# MCU.net
KiCad netlist of a schematic drawn in Altium Designer
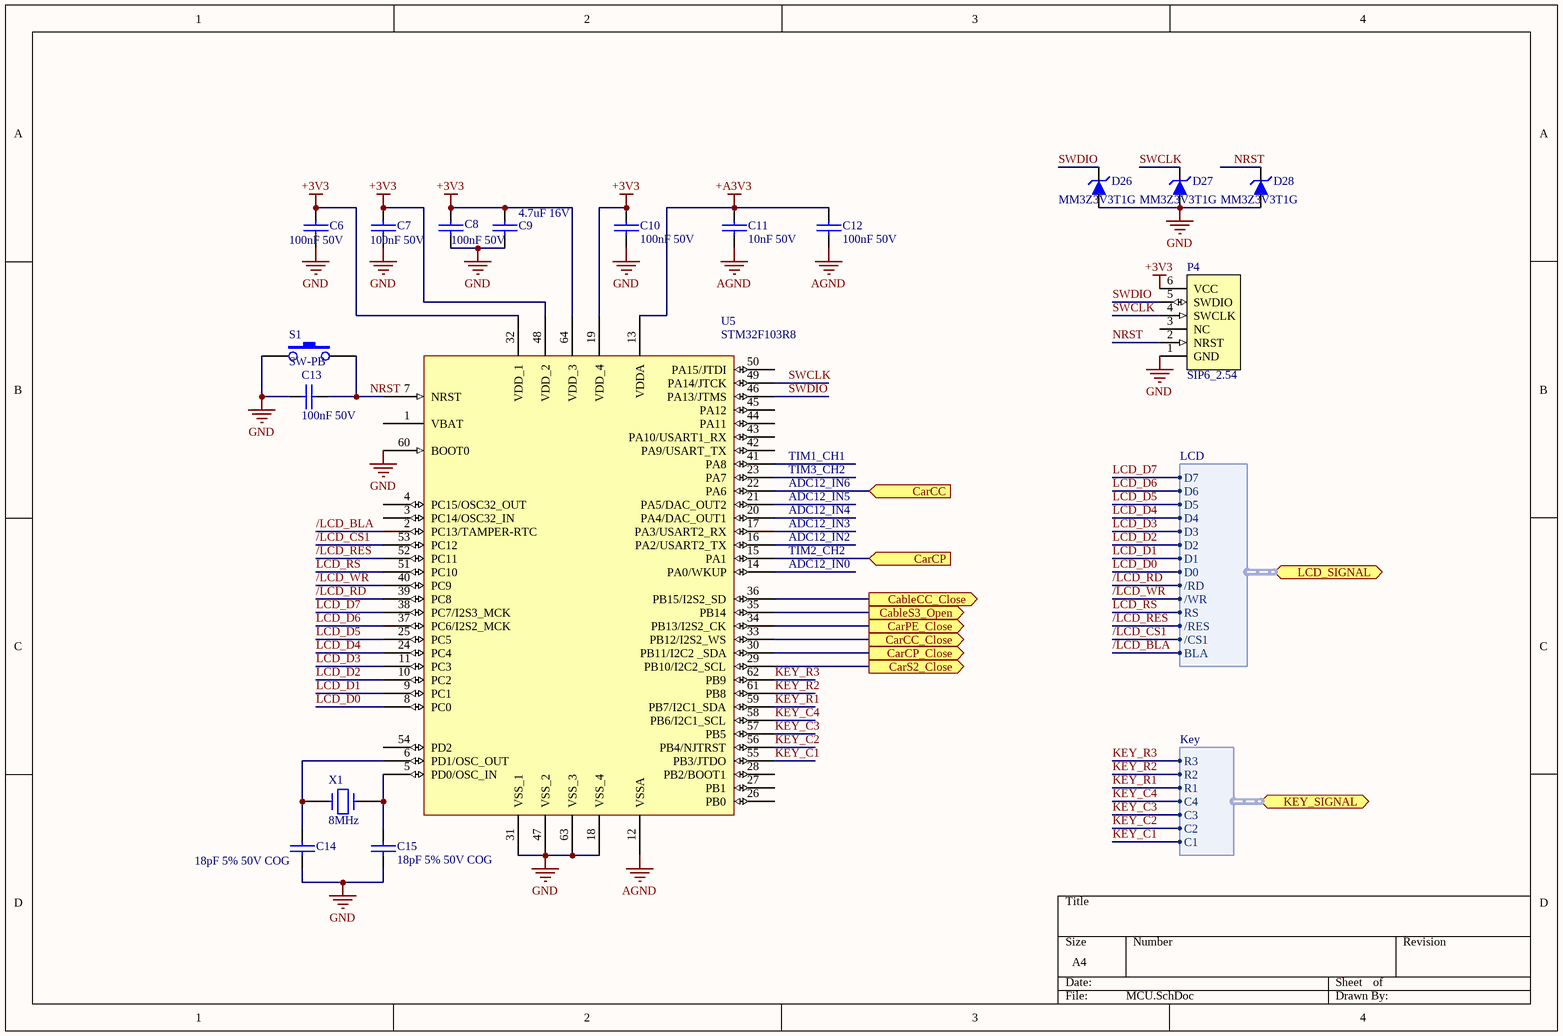
[diagram p0: MCU.SchDoc]

(export (version "E")
  (design (tool "Eeschema 10.0.6"))
  (components
    (comp (ref "C6")
      (value "100nF 50V")
      (footprint "Chip_Capacitor_N:CAPC2012N")
      (description "Capacitor")
      (libsource (lib "*") (part "CAP"))
    )
    (comp (ref "C7")
      (value "100nF 50V")
      (footprint "Chip_Capacitor_N:CAPC2012N")
      (description "Capacitor")
      (libsource (lib "*") (part "CAP"))
    )
    (comp (ref "C8")
      (value "100nF 50V")
      (footprint "Chip_Capacitor_N:CAPC2012N")
      (description "Capacitor")
      (libsource (lib "*") (part "CAP"))
    )
    (comp (ref "C9")
      (value "4.7uF 16V")
      (footprint "Chip_Capacitor_N:CAPC2012N")
      (description "Capacitor")
      (libsource (lib "*") (part "CAP"))
    )
    (comp (ref "C10")
      (value "100nF 50V")
      (footprint "Chip_Capacitor_N:CAPC2012N")
      (description "Capacitor")
      (libsource (lib "*") (part "CAP"))
    )
    (comp (ref "C11")
      (value "10nF 50V")
      (footprint "Chip_Capacitor_N:CAPC2012N")
      (description "Capacitor")
      (libsource (lib "*") (part "CAP"))
    )
    (comp (ref "C12")
      (value "100nF 50V")
      (footprint "Chip_Capacitor_N:CAPC2012N")
      (description "Capacitor")
      (libsource (lib "*") (part "CAP"))
    )
    (comp (ref "C13")
      (value "100nF 50V")
      (footprint "Chip_Capacitor_N:CAPC2012N")
      (description "Capacitor")
      (libsource (lib "*") (part "CAP"))
    )
    (comp (ref "C14")
      (value "18pF 5% 50V COG")
      (footprint "Chip_Capacitor_N:CAPC2012N")
      (description "Capacitor")
      (libsource (lib "*") (part "CAP"))
    )
    (comp (ref "C15")
      (value "18pF 5% 50V COG")
      (footprint "Chip_Capacitor_N:CAPC2012N")
      (description "Capacitor")
      (libsource (lib "*") (part "CAP"))
    )
    (comp (ref "D26")
      (value "MM3Z3V3T1G")
      (footprint "Small Outline Diode - 2 Gullwing Leads:SOD-323")
      (description "Zener diode")
      (fields (field (name "MANUFACTURER") "ON"))
      (libsource (lib "UserSchlib") (part "Zener Diode"))
    )
    (comp (ref "D27")
      (value "MM3Z3V3T1G")
      (footprint "Small Outline Diode - 2 Gullwing Leads:SOD-323")
      (description "Zener diode")
      (fields (field (name "MANUFACTURER") "ON"))
      (libsource (lib "UserSchlib") (part "Zener Diode"))
    )
    (comp (ref "D28")
      (value "MM3Z3V3T1G")
      (footprint "Small Outline Diode - 2 Gullwing Leads:SOD-323")
      (description "Zener diode")
      (fields (field (name "MANUFACTURER") "ON"))
      (libsource (lib "UserSchlib") (part "Zener Diode"))
    )
    (comp (ref "P4")
      (value "SIP6_2.54")
      (footprint "UserPcbLib:REAL_SIP6_2.54")
      (description "SW debug connector")
      (libsource (lib "UserSchlib") (part "SWD-Connector"))
    )
    (comp (ref "S1") (value "SW-PB") (footprint "UserPcbLib:SW5X7") (libsource (lib "*") (part "SW-PB")))
    (comp (ref "U5")
      (value "STM32F103R8")
      (footprint "ST-Microelectronics Footprints:TQFP64_M")
      (libsource (lib "Peter") (part "STM32F105RX"))
    )
    (comp (ref "X1")
      (value "8MHz")
      (footprint "ATSM-49")
      (description "晶振")
      (libsource (lib "*") (part "CRYSTAL"))
    )
  )
  (nets
    (net (code "3") (name "+3V3") (class "Default")
      (node (ref "C10") (pin "1") (pinfunction "1_1") (pintype "passive"))
      (node (ref "C6") (pin "2") (pinfunction "2_2") (pintype "passive"))
      (node (ref "C7") (pin "1") (pinfunction "1_1") (pintype "passive"))
      (node (ref "C8") (pin "1") (pinfunction "1_1") (pintype "passive"))
      (node (ref "C9") (pin "1") (pinfunction "1_1") (pintype "passive"))
      (node (ref "P4") (pin "6") (pinfunction "VCC_6") (pintype "power_in"))
      (node (ref "U5") (pin "19") (pinfunction "VDD_4_19") (pintype "power_in"))
      (node (ref "U5") (pin "32") (pinfunction "VDD_1_32") (pintype "power_in"))
      (node (ref "U5") (pin "48") (pinfunction "VDD_2_48") (pintype "power_in"))
      (node (ref "U5") (pin "64") (pinfunction "VDD_3_64") (pintype "power_in"))
    )
    (net (code "4") (name "+A3V3") (class "Default")
      (node (ref "C11") (pin "1") (pinfunction "1_1") (pintype "passive"))
      (node (ref "C12") (pin "1") (pinfunction "1_1") (pintype "passive"))
      (node (ref "U5") (pin "13") (pinfunction "VDDA_13") (pintype "power_in"))
    )
    (net (code "5") (name "/CableCC_Close") (class "Default")
      (node (ref "U5") (pin "36") (pinfunction "PB15/I2S2_SD_36") (pintype "bidirectional"))
    )
    (net (code "6") (name "/CableS3_Open") (class "Default")
      (node (ref "U5") (pin "35") (pinfunction "PB14_35") (pintype "bidirectional"))
    )
    (net (code "7") (name "/CarCC") (class "Default")
      (node (ref "U5") (pin "22") (pinfunction "PA6_22") (pintype "bidirectional"))
    )
    (net (code "8") (name "/CarCC_Close") (class "Default")
      (node (ref "U5") (pin "33") (pinfunction "PB12/I2S2_WS_33") (pintype "bidirectional"))
    )
    (net (code "9") (name "/CarCP") (class "Default")
      (node (ref "U5") (pin "15") (pinfunction "PA1_15") (pintype "bidirectional"))
    )
    (net (code "10") (name "/CarCP_Close") (class "Default")
      (node (ref "U5") (pin "30") (pinfunction "PB11/I2C2__SDA_30") (pintype "bidirectional"))
    )
    (net (code "11") (name "/CarPE_Close") (class "Default")
      (node (ref "U5") (pin "34") (pinfunction "PB13/I2S2_CK_34") (pintype "bidirectional"))
    )
    (net (code "12") (name "/CarS2_Close") (class "Default")
      (node (ref "U5") (pin "29") (pinfunction "PB10/I2C2_SCL_29") (pintype "bidirectional"))
    )
    (net (code "13") (name "/KEY_C1") (class "Default")
      (node (ref "U5") (pin "55") (pinfunction "PB3/JTDO_55") (pintype "bidirectional"))
    )
    (net (code "14") (name "/KEY_C2") (class "Default")
      (node (ref "U5") (pin "56") (pinfunction "PB4/NJTRST_56") (pintype "bidirectional"))
    )
    (net (code "15") (name "/KEY_C3") (class "Default")
      (node (ref "U5") (pin "57") (pinfunction "PB5_57") (pintype "bidirectional"))
    )
    (net (code "16") (name "/KEY_C4") (class "Default")
      (node (ref "U5") (pin "58") (pinfunction "PB6/I2C1_SCL_58") (pintype "bidirectional"))
    )
    (net (code "17") (name "/KEY_R1") (class "Default")
      (node (ref "U5") (pin "59") (pinfunction "PB7/I2C1_SDA_59") (pintype "bidirectional"))
    )
    (net (code "18") (name "/KEY_R2") (class "Default")
      (node (ref "U5") (pin "61") (pinfunction "PB8_61") (pintype "bidirectional"))
    )
    (net (code "19") (name "/KEY_R3") (class "Default")
      (node (ref "U5") (pin "62") (pinfunction "PB9_62") (pintype "bidirectional"))
    )
    (net (code "20") (name "/LCD_D0") (class "Default")
      (node (ref "U5") (pin "8") (pinfunction "PC0_8") (pintype "bidirectional"))
    )
    (net (code "21") (name "/LCD_D1") (class "Default")
      (node (ref "U5") (pin "9") (pinfunction "PC1_9") (pintype "bidirectional"))
    )
    (net (code "22") (name "/LCD_D2") (class "Default")
      (node (ref "U5") (pin "10") (pinfunction "PC2_10") (pintype "bidirectional"))
    )
    (net (code "23") (name "/LCD_D3") (class "Default")
      (node (ref "U5") (pin "11") (pinfunction "PC3_11") (pintype "bidirectional"))
    )
    (net (code "24") (name "/LCD_D4") (class "Default")
      (node (ref "U5") (pin "24") (pinfunction "PC4_24") (pintype "bidirectional"))
    )
    (net (code "25") (name "/LCD_D5") (class "Default")
      (node (ref "U5") (pin "25") (pinfunction "PC5_25") (pintype "bidirectional"))
    )
    (net (code "26") (name "/LCD_D6") (class "Default")
      (node (ref "U5") (pin "37") (pinfunction "PC6/I2S2_MCK_37") (pintype "bidirectional"))
    )
    (net (code "27") (name "/LCD_D7") (class "Default")
      (node (ref "U5") (pin "38") (pinfunction "PC7/I2S3_MCK_38") (pintype "bidirectional"))
    )
    (net (code "28") (name "/LCD_RS") (class "Default")
      (node (ref "U5") (pin "51") (pinfunction "PC10_51") (pintype "bidirectional"))
    )
    (net (code "29") (name "/NRST") (class "Default")
      (node (ref "C13") (pin "1") (pinfunction "1_1") (pintype "passive"))
      (node (ref "D28") (pin "1") (pinfunction "K_1") (pintype "passive"))
      (node (ref "P4") (pin "2") (pinfunction "NRST_2") (pintype "input"))
      (node (ref "S1") (pin "2") (pinfunction "2_2") (pintype "passive"))
      (node (ref "U5") (pin "7") (pinfunction "NRST_7") (pintype "input"))
    )
    (net (code "30") (name "/SWCLK") (class "Default")
      (node (ref "D27") (pin "1") (pinfunction "K_1") (pintype "passive"))
      (node (ref "P4") (pin "4") (pinfunction "SWCLK_4") (pintype "input"))
      (node (ref "U5") (pin "49") (pinfunction "PA14/JTCK_49") (pintype "bidirectional"))
    )
    (net (code "31") (name "/SWDIO") (class "Default")
      (node (ref "D26") (pin "1") (pinfunction "K_1") (pintype "passive"))
      (node (ref "P4") (pin "5") (pinfunction "SWDIO_5") (pintype "bidirectional"))
      (node (ref "U5") (pin "46") (pinfunction "PA13/JTMS_46") (pintype "bidirectional"))
    )
    (net (code "34") (name "/{slash}LCD_BLA") (class "Default")
      (node (ref "U5") (pin "2") (pinfunction "PC13/TAMPER-RTC_2") (pintype "bidirectional"))
    )
    (net (code "35") (name "/{slash}LCD_CS1") (class "Default")
      (node (ref "U5") (pin "53") (pinfunction "PC12_53") (pintype "bidirectional"))
    )
    (net (code "36") (name "/{slash}LCD_RD") (class "Default")
      (node (ref "U5") (pin "39") (pinfunction "PC8_39") (pintype "bidirectional"))
    )
    (net (code "37") (name "/{slash}LCD_RES") (class "Default")
      (node (ref "U5") (pin "52") (pinfunction "PC11_52") (pintype "bidirectional"))
    )
    (net (code "38") (name "/{slash}LCD_WR") (class "Default")
      (node (ref "U5") (pin "40") (pinfunction "PC9_40") (pintype "bidirectional"))
    )
    (net (code "39") (name "AGND") (class "Default")
      (node (ref "C11") (pin "2") (pinfunction "2_2") (pintype "passive"))
      (node (ref "C12") (pin "2") (pinfunction "2_2") (pintype "passive"))
      (node (ref "U5") (pin "12") (pinfunction "VSSA_12") (pintype "power_in"))
    )
    (net (code "40") (name "GND") (class "Default")
      (node (ref "C10") (pin "2") (pinfunction "2_2") (pintype "passive"))
      (node (ref "C13") (pin "2") (pinfunction "2_2") (pintype "passive"))
      (node (ref "C14") (pin "2") (pinfunction "2_2") (pintype "passive"))
      (node (ref "C15") (pin "1") (pinfunction "1_1") (pintype "passive"))
      (node (ref "C6") (pin "1") (pinfunction "1_1") (pintype "passive"))
      (node (ref "C7") (pin "2") (pinfunction "2_2") (pintype "passive"))
      (node (ref "C8") (pin "2") (pinfunction "2_2") (pintype "passive"))
      (node (ref "C9") (pin "2") (pinfunction "2_2") (pintype "passive"))
      (node (ref "D26") (pin "2") (pinfunction "A_2") (pintype "passive"))
      (node (ref "D27") (pin "2") (pinfunction "A_2") (pintype "passive"))
      (node (ref "D28") (pin "2") (pinfunction "A_2") (pintype "passive"))
      (node (ref "P4") (pin "1") (pinfunction "GND_1") (pintype "power_in"))
      (node (ref "S1") (pin "1") (pinfunction "1_1") (pintype "passive"))
      (node (ref "U5") (pin "18") (pinfunction "VSS_4_18") (pintype "power_in"))
      (node (ref "U5") (pin "31") (pinfunction "VSS_1_31") (pintype "power_in"))
      (node (ref "U5") (pin "47") (pinfunction "VSS_2_47") (pintype "power_in"))
      (node (ref "U5") (pin "60") (pinfunction "BOOT0_60") (pintype "input"))
      (node (ref "U5") (pin "63") (pinfunction "VSS_3_63") (pintype "power_in"))
    )
    (net (code "41") (name "Net-(U5-PD0{slash}OSC_IN)") (class "Default")
      (node (ref "C15") (pin "2") (pinfunction "2_2") (pintype "passive"))
      (node (ref "U5") (pin "5") (pinfunction "PD0/OSC_IN_5") (pintype "bidirectional"))
      (node (ref "X1") (pin "2") (pinfunction "2_2") (pintype "passive"))
    )
    (net (code "42") (name "Net-(U5-PD1{slash}OSC_OUT)") (class "Default")
      (node (ref "C14") (pin "1") (pinfunction "1_1") (pintype "passive"))
      (node (ref "U5") (pin "6") (pinfunction "PD1/OSC_OUT_6") (pintype "bidirectional"))
      (node (ref "X1") (pin "1") (pinfunction "1_1") (pintype "passive"))
    )
    (net (code "43") (name "unconnected-(P4-NC-Pad3)") (class "Default")
      (node (ref "P4") (pin "3") (pinfunction "NC_3") (pintype "power_in"))
    )
    (net (code "44") (name "unconnected-(U5-PA0{slash}WKUP-Pad14)") (class "Default")
      (node (ref "U5") (pin "14") (pinfunction "PA0/WKUP_14") (pintype "bidirectional"))
    )
    (net (code "45") (name "unconnected-(U5-PA2{slash}USART2_TX-Pad16)") (class "Default")
      (node (ref "U5") (pin "16") (pinfunction "PA2/USART2_TX_16") (pintype "bidirectional"))
    )
    (net (code "46") (name "unconnected-(U5-PA3{slash}USART2_RX-Pad17)") (class "Default")
      (node (ref "U5") (pin "17") (pinfunction "PA3/USART2_RX_17") (pintype "bidirectional"))
    )
    (net (code "47") (name "unconnected-(U5-PA4{slash}DAC_OUT1-Pad20)") (class "Default")
      (node (ref "U5") (pin "20") (pinfunction "PA4/DAC_OUT1_20") (pintype "bidirectional"))
    )
    (net (code "48") (name "unconnected-(U5-PA5{slash}DAC_OUT2-Pad21)") (class "Default")
      (node (ref "U5") (pin "21") (pinfunction "PA5/DAC_OUT2_21") (pintype "bidirectional"))
    )
    (net (code "49") (name "unconnected-(U5-PA7-Pad23)") (class "Default")
      (node (ref "U5") (pin "23") (pinfunction "PA7_23") (pintype "bidirectional"))
    )
    (net (code "50") (name "unconnected-(U5-PA8-Pad41)") (class "Default")
      (node (ref "U5") (pin "41") (pinfunction "PA8_41") (pintype "bidirectional"))
    )
    (net (code "51") (name "unconnected-(U5-PA9{slash}USART_TX-Pad42)") (class "Default")
      (node (ref "U5") (pin "42") (pinfunction "PA9/USART_TX_42") (pintype "bidirectional"))
    )
    (net (code "52") (name "unconnected-(U5-PA10{slash}USART1_RX-Pad43)") (class "Default")
      (node (ref "U5") (pin "43") (pinfunction "PA10/USART1_RX_43") (pintype "bidirectional"))
    )
    (net (code "53") (name "unconnected-(U5-PA11-Pad44)") (class "Default")
      (node (ref "U5") (pin "44") (pinfunction "PA11_44") (pintype "bidirectional"))
    )
    (net (code "54") (name "unconnected-(U5-PA12-Pad45)") (class "Default")
      (node (ref "U5") (pin "45") (pinfunction "PA12_45") (pintype "bidirectional"))
    )
    (net (code "55") (name "unconnected-(U5-PA15{slash}JTDI-Pad50)") (class "Default")
      (node (ref "U5") (pin "50") (pinfunction "PA15/JTDI_50") (pintype "bidirectional"))
    )
    (net (code "56") (name "unconnected-(U5-PB0-Pad26)") (class "Default")
      (node (ref "U5") (pin "26") (pinfunction "PB0_26") (pintype "bidirectional"))
    )
    (net (code "57") (name "unconnected-(U5-PB1-Pad27)") (class "Default")
      (node (ref "U5") (pin "27") (pinfunction "PB1_27") (pintype "bidirectional"))
    )
    (net (code "58") (name "unconnected-(U5-PB2{slash}BOOT1-Pad28)") (class "Default")
      (node (ref "U5") (pin "28") (pinfunction "PB2/BOOT1_28") (pintype "bidirectional"))
    )
    (net (code "59") (name "unconnected-(U5-PC14{slash}OSC32_IN-Pad3)") (class "Default")
      (node (ref "U5") (pin "3") (pinfunction "PC14/OSC32_IN_3") (pintype "bidirectional"))
    )
    (net (code "60") (name "unconnected-(U5-PC15{slash}OSC32_OUT-Pad4)") (class "Default")
      (node (ref "U5") (pin "4") (pinfunction "PC15/OSC32_OUT_4") (pintype "bidirectional"))
    )
    (net (code "61") (name "unconnected-(U5-PD2-Pad54)") (class "Default")
      (node (ref "U5") (pin "54") (pinfunction "PD2_54") (pintype "bidirectional"))
    )
    (net (code "62") (name "unconnected-(U5-VBAT-Pad1)") (class "Default")
      (node (ref "U5") (pin "1") (pinfunction "VBAT_1") (pintype "power_in"))
    )
  )
)
